# shieldrasp.net
KiCad netlist of a schematic drawn in EAGLE
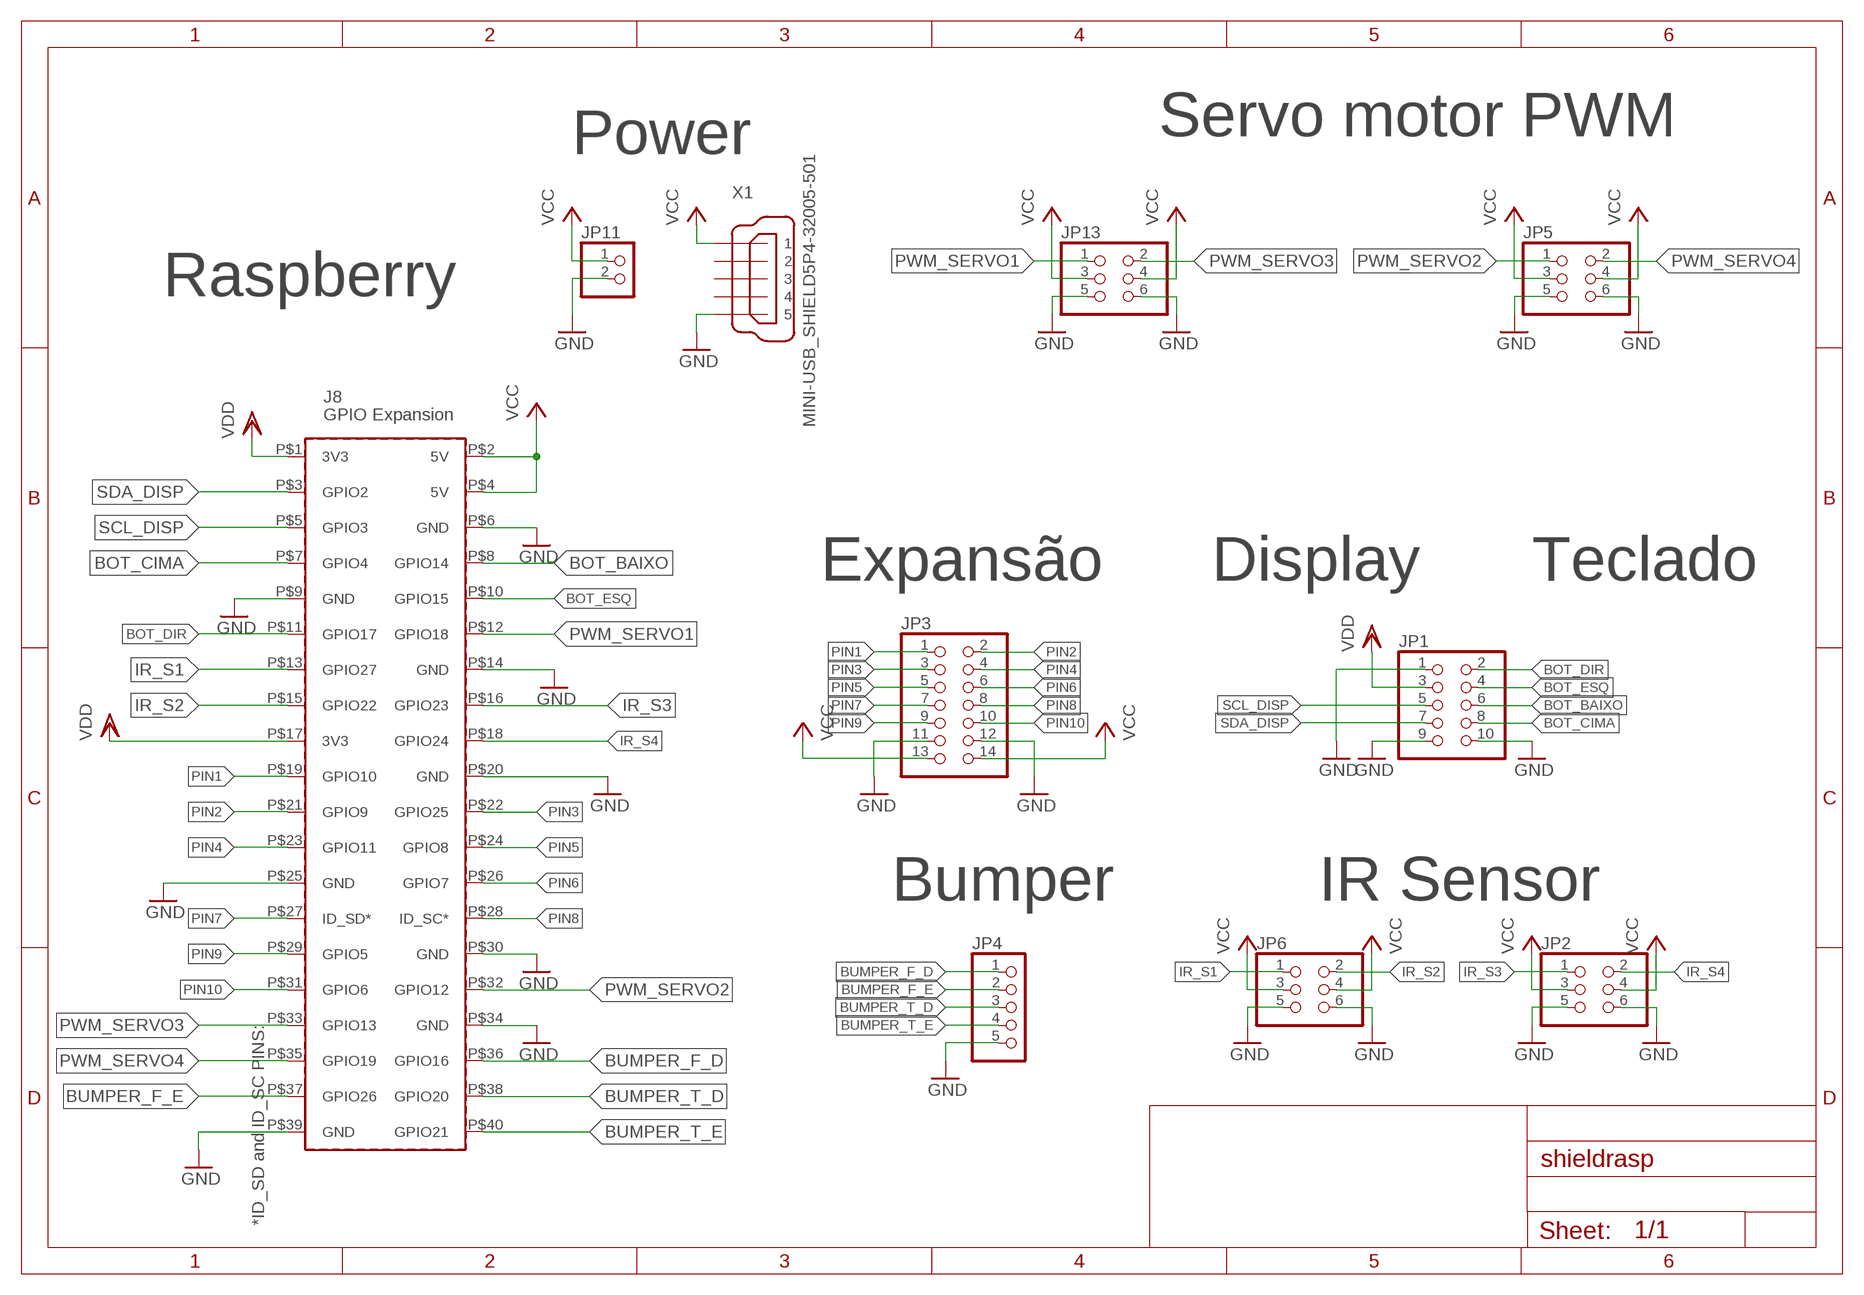
[diagram p0: schematic, sheet 1]

(export (version "E")
  (design (tool "Eeschema 10.0.6"))
  (components
    (comp (ref "JP1")
      (value "PINHD-2X5/90")
      (footprint "eagle-import:2X05_90")
      (libsource (lib "eagle-import") (part "PINHD-2X5/90"))
    )
    (comp (ref "JP2")
      (value "PINHD-2X3/90")
      (footprint "eagle-import:2X03_90")
      (libsource (lib "eagle-import") (part "PINHD-2X3/90"))
    )
    (comp (ref "JP3")
      (value "PINHD-2X7")
      (footprint "eagle-import:2X07")
      (libsource (lib "eagle-import") (part "PINHD-2X7"))
    )
    (comp (ref "JP4")
      (value "PINHD-1X5/90")
      (footprint "eagle-import:1X05_90")
      (libsource (lib "eagle-import") (part "PINHD-1X5/90"))
    )
    (comp (ref "JP5")
      (value "PINHD-2X3/90")
      (footprint "eagle-import:2X03_90")
      (libsource (lib "eagle-import") (part "PINHD-2X3/90"))
    )
    (comp (ref "JP6")
      (value "PINHD-2X3/90")
      (footprint "eagle-import:2X03_90")
      (libsource (lib "eagle-import") (part "PINHD-2X3/90"))
    )
    (comp (ref "JP11")
      (value "PINHD-1X2/90")
      (footprint "eagle-import:1X02_90")
      (libsource (lib "eagle-import") (part "PINHD-1X2/90"))
    )
    (comp (ref "JP13")
      (value "PINHD-2X3/90")
      (footprint "eagle-import:2X03_90")
      (libsource (lib "eagle-import") (part "PINHD-2X3/90"))
    )
    (comp (ref "PCB1")
      (value "RPI3RPI3")
      (footprint "eagle-import:RPI3")
      (libsource (lib "eagle-import") (part "RPI3RPI3"))
    )
    (comp (ref "X1")
      (value "MINI-USB_SHIELD5P4-32005-501")
      (footprint "eagle-import:32005-501")
      (libsource (lib "eagle-import") (part "MINI-USB_SHIELD5P4-32005-501"))
    )
  )
  (nets
    (net (code "1") (name "BOT_BAIXO") (class "Default")
      (node (ref "JP1") (pin "6") (pinfunction "6_6") (pintype "passive"))
      (node (ref "PCB1") (pin "P$8") (pinfunction "GPIO14_P$8") (pintype "bidirectional"))
    )
    (net (code "2") (name "BOT_CIMA") (class "Default")
      (node (ref "JP1") (pin "8") (pinfunction "8_8") (pintype "passive"))
      (node (ref "PCB1") (pin "P$7") (pinfunction "GPIO4_P$7") (pintype "bidirectional"))
    )
    (net (code "3") (name "BOT_DIR") (class "Default")
      (node (ref "JP1") (pin "2") (pinfunction "2_2") (pintype "passive"))
      (node (ref "PCB1") (pin "P$11") (pinfunction "GPIO17_P$11") (pintype "bidirectional"))
    )
    (net (code "4") (name "BOT_ESQ") (class "Default")
      (node (ref "JP1") (pin "4") (pinfunction "4_4") (pintype "passive"))
      (node (ref "PCB1") (pin "P$10") (pinfunction "GPIO15_P$10") (pintype "bidirectional"))
    )
    (net (code "5") (name "BUMPER_F_D") (class "Default")
      (node (ref "JP4") (pin "1") (pinfunction "1_1") (pintype "passive"))
      (node (ref "PCB1") (pin "P$36") (pinfunction "GPIO16_P$36") (pintype "bidirectional"))
    )
    (net (code "6") (name "BUMPER_F_E") (class "Default")
      (node (ref "JP4") (pin "2") (pinfunction "2_2") (pintype "passive"))
      (node (ref "PCB1") (pin "P$37") (pinfunction "GPIO26_P$37") (pintype "bidirectional"))
    )
    (net (code "7") (name "BUMPER_T_D") (class "Default")
      (node (ref "JP4") (pin "3") (pinfunction "3_3") (pintype "passive"))
      (node (ref "PCB1") (pin "P$38") (pinfunction "GPIO20_P$38") (pintype "bidirectional"))
    )
    (net (code "8") (name "BUMPER_T_E") (class "Default")
      (node (ref "JP4") (pin "4") (pinfunction "4_4") (pintype "passive"))
      (node (ref "PCB1") (pin "P$40") (pinfunction "GPIO21_P$40") (pintype "bidirectional"))
    )
    (net (code "9") (name "GND") (class "Default")
      (node (ref "JP1") (pin "1") (pinfunction "1_1") (pintype "passive"))
      (node (ref "JP1") (pin "10") (pinfunction "10_10") (pintype "passive"))
      (node (ref "JP1") (pin "9") (pinfunction "9_9") (pintype "passive"))
      (node (ref "JP11") (pin "2") (pinfunction "2_2") (pintype "passive"))
      (node (ref "JP13") (pin "5") (pinfunction "5_5") (pintype "passive"))
      (node (ref "JP13") (pin "6") (pinfunction "6_6") (pintype "passive"))
      (node (ref "JP2") (pin "5") (pinfunction "5_5") (pintype "passive"))
      (node (ref "JP2") (pin "6") (pinfunction "6_6") (pintype "passive"))
      (node (ref "JP3") (pin "11") (pinfunction "11_11") (pintype "passive"))
      (node (ref "JP3") (pin "12") (pinfunction "12_12") (pintype "passive"))
      (node (ref "JP4") (pin "5") (pinfunction "5_5") (pintype "passive"))
      (node (ref "JP5") (pin "5") (pinfunction "5_5") (pintype "passive"))
      (node (ref "JP5") (pin "6") (pinfunction "6_6") (pintype "passive"))
      (node (ref "JP6") (pin "5") (pinfunction "5_5") (pintype "passive"))
      (node (ref "JP6") (pin "6") (pinfunction "6_6") (pintype "passive"))
      (node (ref "PCB1") (pin "P$14") (pinfunction "GND_P$14") (pintype "bidirectional"))
      (node (ref "PCB1") (pin "P$20") (pinfunction "GND_P$20") (pintype "bidirectional"))
      (node (ref "PCB1") (pin "P$25") (pinfunction "GND_P$25") (pintype "bidirectional"))
      (node (ref "PCB1") (pin "P$30") (pinfunction "GND_P$30") (pintype "bidirectional"))
      (node (ref "PCB1") (pin "P$34") (pinfunction "GND_P$34") (pintype "bidirectional"))
      (node (ref "PCB1") (pin "P$39") (pinfunction "GND_P$39") (pintype "bidirectional"))
      (node (ref "PCB1") (pin "P$6") (pinfunction "GND_P$6") (pintype "bidirectional"))
      (node (ref "PCB1") (pin "P$9") (pinfunction "GND_P$9") (pintype "bidirectional"))
      (node (ref "X1") (pin "5") (pinfunction "5_5") (pintype "passive"))
    )
    (net (code "10") (name "IR_S1") (class "Default")
      (node (ref "JP6") (pin "1") (pinfunction "1_1") (pintype "passive"))
      (node (ref "PCB1") (pin "P$13") (pinfunction "GPIO27_P$13") (pintype "bidirectional"))
    )
    (net (code "11") (name "IR_S2") (class "Default")
      (node (ref "JP6") (pin "2") (pinfunction "2_2") (pintype "passive"))
      (node (ref "PCB1") (pin "P$15") (pinfunction "GPIO22_P$15") (pintype "bidirectional"))
    )
    (net (code "12") (name "IR_S3") (class "Default")
      (node (ref "JP2") (pin "1") (pinfunction "1_1") (pintype "passive"))
      (node (ref "PCB1") (pin "P$16") (pinfunction "GPIO23_P$16") (pintype "bidirectional"))
    )
    (net (code "13") (name "IR_S4") (class "Default")
      (node (ref "JP2") (pin "2") (pinfunction "2_2") (pintype "passive"))
      (node (ref "PCB1") (pin "P$18") (pinfunction "GPIO24_P$18") (pintype "bidirectional"))
    )
    (net (code "14") (name "PIN1") (class "Default")
      (node (ref "JP3") (pin "1") (pinfunction "1_1") (pintype "passive"))
      (node (ref "PCB1") (pin "P$19") (pinfunction "GPIO10_P$19") (pintype "bidirectional"))
    )
    (net (code "15") (name "PIN2") (class "Default")
      (node (ref "JP3") (pin "2") (pinfunction "2_2") (pintype "passive"))
      (node (ref "PCB1") (pin "P$21") (pinfunction "GPIO9_P$21") (pintype "bidirectional"))
    )
    (net (code "16") (name "PIN3") (class "Default")
      (node (ref "JP3") (pin "3") (pinfunction "3_3") (pintype "passive"))
      (node (ref "PCB1") (pin "P$22") (pinfunction "GPIO25_P$22") (pintype "bidirectional"))
    )
    (net (code "17") (name "PIN4") (class "Default")
      (node (ref "JP3") (pin "4") (pinfunction "4_4") (pintype "passive"))
      (node (ref "PCB1") (pin "P$23") (pinfunction "GPIO11_P$23") (pintype "bidirectional"))
    )
    (net (code "18") (name "PIN5") (class "Default")
      (node (ref "JP3") (pin "5") (pinfunction "5_5") (pintype "passive"))
      (node (ref "PCB1") (pin "P$24") (pinfunction "GPIO8_P$24") (pintype "bidirectional"))
    )
    (net (code "19") (name "PIN6") (class "Default")
      (node (ref "JP3") (pin "6") (pinfunction "6_6") (pintype "passive"))
      (node (ref "PCB1") (pin "P$26") (pinfunction "GPIO7_P$26") (pintype "bidirectional"))
    )
    (net (code "20") (name "PIN7") (class "Default")
      (node (ref "JP3") (pin "7") (pinfunction "7_7") (pintype "passive"))
      (node (ref "PCB1") (pin "P$27") (pinfunction "ID_SD*_P$27") (pintype "bidirectional"))
    )
    (net (code "21") (name "PIN8") (class "Default")
      (node (ref "JP3") (pin "8") (pinfunction "8_8") (pintype "passive"))
      (node (ref "PCB1") (pin "P$28") (pinfunction "ID_SC*_P$28") (pintype "bidirectional"))
    )
    (net (code "22") (name "PIN9") (class "Default")
      (node (ref "JP3") (pin "9") (pinfunction "9_9") (pintype "passive"))
      (node (ref "PCB1") (pin "P$29") (pinfunction "GPIO5_P$29") (pintype "bidirectional"))
    )
    (net (code "23") (name "PIN10") (class "Default")
      (node (ref "JP3") (pin "10") (pinfunction "10_10") (pintype "passive"))
      (node (ref "PCB1") (pin "P$31") (pinfunction "GPIO6_P$31") (pintype "bidirectional"))
    )
    (net (code "24") (name "PWM_SERVO1") (class "Default")
      (node (ref "JP13") (pin "1") (pinfunction "1_1") (pintype "passive"))
      (node (ref "PCB1") (pin "P$12") (pinfunction "GPIO18_P$12") (pintype "bidirectional"))
    )
    (net (code "25") (name "PWM_SERVO2") (class "Default")
      (node (ref "JP5") (pin "1") (pinfunction "1_1") (pintype "passive"))
      (node (ref "PCB1") (pin "P$32") (pinfunction "GPIO12_P$32") (pintype "bidirectional"))
    )
    (net (code "26") (name "PWM_SERVO3") (class "Default")
      (node (ref "JP13") (pin "2") (pinfunction "2_2") (pintype "passive"))
      (node (ref "PCB1") (pin "P$33") (pinfunction "GPIO13_P$33") (pintype "bidirectional"))
    )
    (net (code "27") (name "PWM_SERVO4") (class "Default")
      (node (ref "JP5") (pin "2") (pinfunction "2_2") (pintype "passive"))
      (node (ref "PCB1") (pin "P$35") (pinfunction "GPIO19_P$35") (pintype "bidirectional"))
    )
    (net (code "28") (name "SCL_DISP") (class "Default")
      (node (ref "JP1") (pin "5") (pinfunction "5_5") (pintype "passive"))
      (node (ref "PCB1") (pin "P$5") (pinfunction "GPIO3_P$5") (pintype "bidirectional"))
    )
    (net (code "29") (name "SDA_DISP") (class "Default")
      (node (ref "JP1") (pin "7") (pinfunction "7_7") (pintype "passive"))
      (node (ref "PCB1") (pin "P$3") (pinfunction "GPIO2_P$3") (pintype "bidirectional"))
    )
    (net (code "30") (name "VCC") (class "Default")
      (node (ref "JP11") (pin "1") (pinfunction "1_1") (pintype "passive"))
      (node (ref "JP13") (pin "3") (pinfunction "3_3") (pintype "passive"))
      (node (ref "JP13") (pin "4") (pinfunction "4_4") (pintype "passive"))
      (node (ref "JP2") (pin "3") (pinfunction "3_3") (pintype "passive"))
      (node (ref "JP2") (pin "4") (pinfunction "4_4") (pintype "passive"))
      (node (ref "JP3") (pin "13") (pinfunction "13_13") (pintype "passive"))
      (node (ref "JP3") (pin "14") (pinfunction "14_14") (pintype "passive"))
      (node (ref "JP5") (pin "3") (pinfunction "3_3") (pintype "passive"))
      (node (ref "JP5") (pin "4") (pinfunction "4_4") (pintype "passive"))
      (node (ref "JP6") (pin "3") (pinfunction "3_3") (pintype "passive"))
      (node (ref "JP6") (pin "4") (pinfunction "4_4") (pintype "passive"))
      (node (ref "PCB1") (pin "P$2") (pinfunction "5V_P$2") (pintype "bidirectional"))
      (node (ref "PCB1") (pin "P$4") (pinfunction "5V_P$4") (pintype "bidirectional"))
      (node (ref "X1") (pin "1") (pinfunction "1_1") (pintype "passive"))
    )
    (net (code "31") (name "VDD") (class "Default")
      (node (ref "JP1") (pin "3") (pinfunction "3_3") (pintype "passive"))
      (node (ref "PCB1") (pin "P$1") (pinfunction "3V3_P$1") (pintype "bidirectional"))
      (node (ref "PCB1") (pin "P$17") (pinfunction "3V3_P$17") (pintype "bidirectional"))
    )
    (net (code "32") (name "unconnected-(X1-Pad2)") (class "Default")
      (node (ref "X1") (pin "2") (pinfunction "2_2") (pintype "passive"))
    )
    (net (code "33") (name "unconnected-(X1-Pad3)") (class "Default")
      (node (ref "X1") (pin "3") (pinfunction "3_3") (pintype "passive"))
    )
    (net (code "34") (name "unconnected-(X1-Pad4)") (class "Default")
      (node (ref "X1") (pin "4") (pinfunction "4_4") (pintype "passive"))
    )
  )
)
